# OptoIsolatorFTDI.net
KiCad netlist of a schematic drawn in EAGLE
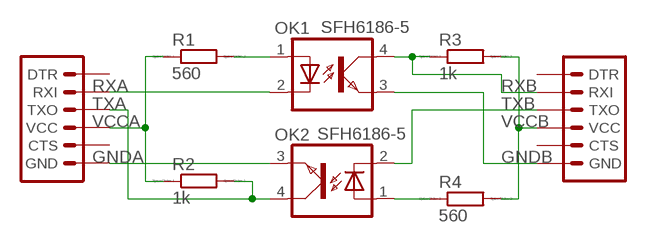
[diagram p0: schematic, sheet 1]

(export (version "E")
  (design (tool "Eeschema 10.0.6"))
  (components
    (comp (ref "JP1")
      (value "FTDI")
      (footprint "eagle-import:1X06")
      (libsource (lib "eagle-import") (part "6_PIN_SERIAL_TARGET"))
    )
    (comp (ref "JP2")
      (value "FTDI_BASICPTH")
      (footprint "eagle-import:1X06")
      (libsource (lib "eagle-import") (part "6_PIN_SERIAL_TARGET"))
    )
    (comp (ref "OK1")
      (value "SFH6186-5")
      (footprint "eagle-import:SMD4-7")
      (fields (field (name "MF") "VISHAY/TELEFUNKEN"))
      (libsource (lib "eagle-import") (part "SFH618?6-5"))
    )
    (comp (ref "OK2")
      (value "SFH6186-5")
      (footprint "eagle-import:SMD4-7")
      (fields (field (name "MF") "VISHAY/TELEFUNKEN"))
      (libsource (lib "eagle-import") (part "SFH618?6-5"))
    )
    (comp (ref "R1")
      (value "560")
      (footprint "eagle-import:R0603")
      (libsource (lib "eagle-import") (part "RR0603"))
    )
    (comp (ref "R2")
      (value "1k")
      (footprint "eagle-import:R0603")
      (libsource (lib "eagle-import") (part "RR0603"))
    )
    (comp (ref "R3")
      (value "1k")
      (footprint "eagle-import:R0603")
      (libsource (lib "eagle-import") (part "RR0603"))
    )
    (comp (ref "R4")
      (value "560")
      (footprint "eagle-import:R0603")
      (libsource (lib "eagle-import") (part "RR0603"))
    )
  )
  (nets
    (net (code "1") (name "/GNDA") (class "Default")
      (node (ref "JP2") (pin "6") (pinfunction "GND_6") (pintype "passive"))
      (node (ref "OK2") (pin "3") (pinfunction "EMIT_3") (pintype "passive"))
    )
    (net (code "2") (name "/GNDB") (class "Default")
      (node (ref "JP1") (pin "6") (pinfunction "GND_6") (pintype "passive"))
      (node (ref "OK1") (pin "3") (pinfunction "EMIT_3") (pintype "passive"))
    )
    (net (code "3") (name "/RXA") (class "Default")
      (node (ref "JP2") (pin "2") (pinfunction "RXI_2") (pintype "passive"))
      (node (ref "OK1") (pin "2") (pinfunction "C_2") (pintype "passive"))
    )
    (net (code "4") (name "/RXB") (class "Default")
      (node (ref "JP1") (pin "2") (pinfunction "RXI_2") (pintype "passive"))
      (node (ref "OK1") (pin "4") (pinfunction "COL_4") (pintype "passive"))
      (node (ref "R3") (pin "1") (pinfunction "1_1") (pintype "passive"))
    )
    (net (code "5") (name "/TXA") (class "Default")
      (node (ref "JP2") (pin "3") (pinfunction "TXO_3") (pintype "passive"))
      (node (ref "OK2") (pin "4") (pinfunction "COL_4") (pintype "passive"))
      (node (ref "R2") (pin "2") (pinfunction "2_2") (pintype "passive"))
    )
    (net (code "6") (name "/TXB") (class "Default")
      (node (ref "JP1") (pin "3") (pinfunction "TXO_3") (pintype "passive"))
      (node (ref "OK2") (pin "2") (pinfunction "C_2") (pintype "passive"))
    )
    (net (code "7") (name "/VCCA") (class "Default")
      (node (ref "JP2") (pin "4") (pinfunction "VCC_4") (pintype "passive"))
      (node (ref "R1") (pin "1") (pinfunction "1_1") (pintype "passive"))
      (node (ref "R2") (pin "1") (pinfunction "1_1") (pintype "passive"))
    )
    (net (code "8") (name "/VCCB") (class "Default")
      (node (ref "JP1") (pin "4") (pinfunction "VCC_4") (pintype "passive"))
      (node (ref "R3") (pin "2") (pinfunction "2_2") (pintype "passive"))
      (node (ref "R4") (pin "2") (pinfunction "2_2") (pintype "passive"))
    )
    (net (code "9") (name "Net-(OK1-A)") (class "Default")
      (node (ref "OK1") (pin "1") (pinfunction "A_1") (pintype "passive"))
      (node (ref "R1") (pin "2") (pinfunction "2_2") (pintype "passive"))
    )
    (net (code "10") (name "Net-(OK2-A)") (class "Default")
      (node (ref "OK2") (pin "1") (pinfunction "A_1") (pintype "passive"))
      (node (ref "R4") (pin "1") (pinfunction "1_1") (pintype "passive"))
    )
    (net (code "11") (name "unconnected-(JP1-CTS-Pad5)") (class "Default")
      (node (ref "JP1") (pin "5") (pinfunction "CTS_5") (pintype "passive"))
    )
    (net (code "12") (name "unconnected-(JP1-DTR-Pad1)") (class "Default")
      (node (ref "JP1") (pin "1") (pinfunction "DTR_1") (pintype "passive"))
    )
    (net (code "13") (name "unconnected-(JP2-CTS-Pad5)") (class "Default")
      (node (ref "JP2") (pin "5") (pinfunction "CTS_5") (pintype "passive"))
    )
    (net (code "14") (name "unconnected-(JP2-DTR-Pad1)") (class "Default")
      (node (ref "JP2") (pin "1") (pinfunction "DTR_1") (pintype "passive"))
    )
  )
)
